# BRD9057A_SiWx917M_4-Layer_ExtSw_REF_DES_.net
KiCad netlist of a schematic drawn in Altium Designer
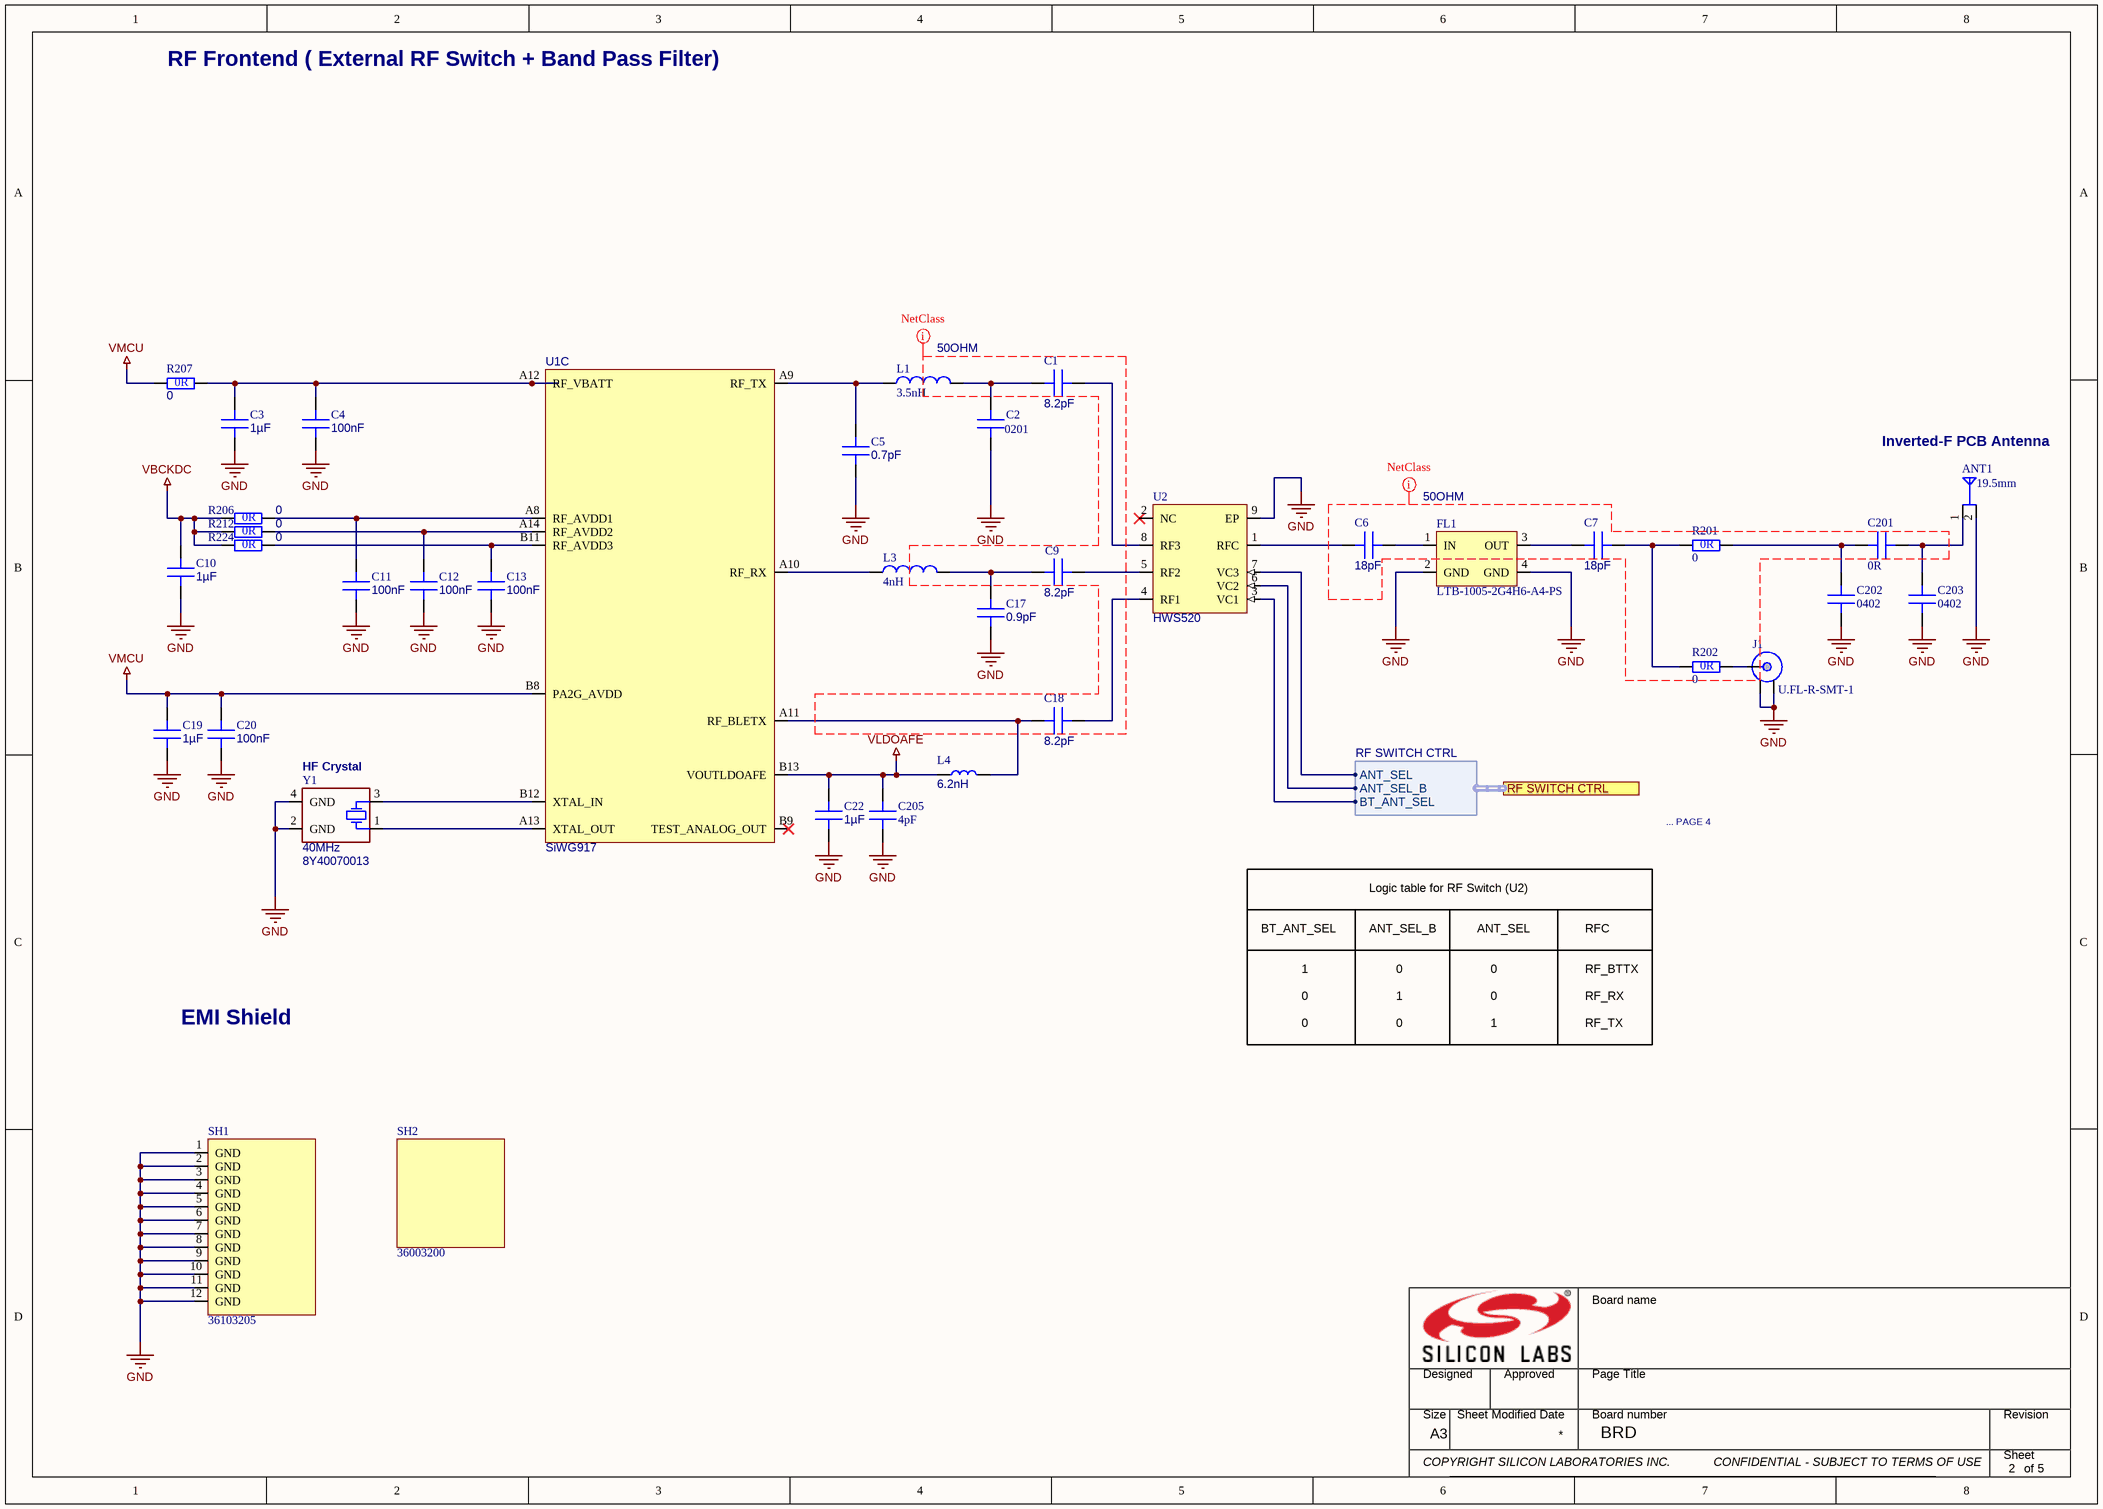
[diagram p0: BRD9057A_SiWx917M_4-Layer_ExtSw_REF_DES_A01_Page_2.SchDoc]

(export (version "E")
  (design (tool "Eeschema 10.0.6"))
  (components
    (comp (ref "ANT1")
      (value "19.5mm")
      (footprint "EM358x_INVERTED_F")
      (description "ANT PATCH 19.5MM INVERTED-F")
      (fields (field (name "Comment") "PATCH ANT INVERTED-F"))
      (libsource (lib "SiLabs Production Server") (part "Patch_Antenna 2-Pin(NO BOM)"))
    )
    (comp (ref "C1")
      (value "8.2pF")
      (footprint "C0201_GM")
      (description "CAP CER 0201 C0G 8.2pF 25V ±0.1pF")
      (fields (field (name "TOLERANCE") "0.1pF") (field (name "MANUFACTURER") "Murata"))
      (libsource (lib "SiLabs Production Server") (part "Capacitor"))
    )
    (comp (ref "C2")
      (value "0201")
      (footprint "C0201_GM")
      (description "Placeholder for 0201 Capacitors")
      (fields (field (name "Comment") "TBD CAP 0201"))
      (libsource (lib "SiLabs Production Server") (part "Placeholder for Capacitor"))
    )
    (comp (ref "C3")
      (value "1µF")
      (footprint "C0201_GM")
      (description "CAP CER 0201 X5R 1uF 16V 20%")
      (fields (field (name "TOLERANCE") "20%"))
      (libsource (lib "SiLabs Production Server") (part "Capacitor"))
    )
    (comp (ref "C4")
      (value "100nF")
      (footprint "C0201_GM")
      (description "CAP CER 0201 X5R 100nF 16V 10%")
      (fields (field (name "TOLERANCE") "10%"))
      (libsource (lib "SiLabs Production Server") (part "Capacitor"))
    )
    (comp (ref "C5")
      (value "0.7pF")
      (footprint "C0201_GM")
      (description "CAP CER 0201 C0G 0.7pF 50V ±0.05pF")
      (fields (field (name "MANUFACTURER") "Murata") (field (name "TOLERANCE") "0.05pF"))
      (libsource (lib "BRD9057A SiWx917 4-layer Ext Switch") (part "GRM0335C1HR70WA01"))
    )
    (comp (ref "C6")
      (value "18pF")
      (footprint "C0201_GM")
      (description "CAP CER 0201 C0G 18pF 50V 2%")
      (fields (field (name "TOLERANCE") "2%") (field (name "MANUFACTURER") "Murata"))
      (libsource (lib "SiLabs Production Server") (part "Capacitor"))
    )
    (comp (ref "C7")
      (value "18pF")
      (footprint "C0201_GM")
      (description "CAP CER 0201 C0G 18pF 50V 2%")
      (fields (field (name "TOLERANCE") "2%") (field (name "MANUFACTURER") "Murata"))
      (libsource (lib "SiLabs Production Server") (part "Capacitor"))
    )
    (comp (ref "C9")
      (value "8.2pF")
      (footprint "C0201_GM")
      (description "CAP CER 0201 C0G 8.2pF 25V ±0.1pF")
      (fields (field (name "TOLERANCE") "0.1pF") (field (name "MANUFACTURER") "Murata"))
      (libsource (lib "SiLabs Production Server") (part "Capacitor"))
    )
    (comp (ref "C10")
      (value "1µF")
      (footprint "C0201_GM")
      (description "CAP CER 0201 X5R 1uF 16V 20%")
      (fields (field (name "TOLERANCE") "20%"))
      (libsource (lib "SiLabs Production Server") (part "Capacitor"))
    )
    (comp (ref "C11")
      (value "100nF")
      (footprint "C0201_GM")
      (description "CAP CER 0201 X5R 100nF 16V 10%")
      (fields (field (name "TOLERANCE") "10%"))
      (libsource (lib "SiLabs Production Server") (part "Capacitor"))
    )
    (comp (ref "C12")
      (value "100nF")
      (footprint "C0201_GM")
      (description "CAP CER 0201 X5R 100nF 16V 10%")
      (fields (field (name "TOLERANCE") "10%"))
      (libsource (lib "SiLabs Production Server") (part "Capacitor"))
    )
    (comp (ref "C13")
      (value "100nF")
      (footprint "C0201_GM")
      (description "CAP CER 0201 X5R 100nF 16V 10%")
      (fields (field (name "TOLERANCE") "10%"))
      (libsource (lib "SiLabs Production Server") (part "Capacitor"))
    )
    (comp (ref "C17")
      (value "0.9pF")
      (footprint "C0201_GM")
      (description "CAP CER 0201 C0G 0.9pF 50V ±0.05pF")
      (fields (field (name "MANUFACTURER") "Murata") (field (name "TOLERANCE") "0.05pF"))
      (libsource (lib "BRD9057A SiWx917 4-layer Ext Switch") (part "GRM0335C1HR90WA01"))
    )
    (comp (ref "C18")
      (value "8.2pF")
      (footprint "C0201_GM")
      (description "CAP CER 0201 C0G 8.2pF 25V ±0.1pF")
      (fields (field (name "TOLERANCE") "0.1pF") (field (name "MANUFACTURER") "Murata"))
      (libsource (lib "SiLabs Production Server") (part "Capacitor"))
    )
    (comp (ref "C19")
      (value "1µF")
      (footprint "C0201_GM")
      (description "CAP CER 0201 X5R 1uF 16V 20%")
      (fields (field (name "TOLERANCE") "20%"))
      (libsource (lib "SiLabs Production Server") (part "Capacitor"))
    )
    (comp (ref "C20")
      (value "100nF")
      (footprint "C0201_GM")
      (description "CAP CER 0201 X5R 100nF 16V 10%")
      (fields (field (name "TOLERANCE") "10%"))
      (libsource (lib "SiLabs Production Server") (part "Capacitor"))
    )
    (comp (ref "C22")
      (value "1µF")
      (footprint "C0201_GM")
      (description "CAP CER 0201 X5R 1uF 16V 20%")
      (fields (field (name "TOLERANCE") "20%"))
      (libsource (lib "SiLabs Production Server") (part "Capacitor"))
    )
    (comp (ref "C201")
      (value "0R")
      (footprint "C0402")
      (description "Placeholder for 0402 Capacitors")
      (fields (field (name "Comment") "TBD CAP 0402"))
      (libsource (lib "SiLabs Production Server") (part "Placeholder for Capacitor"))
    )
    (comp (ref "C202")
      (value "0402")
      (footprint "C0402")
      (description "Placeholder for 0402 Capacitors")
      (fields (field (name "Comment") "TBD CAP 0402"))
      (libsource (lib "SiLabs Production Server") (part "Placeholder for Capacitor"))
    )
    (comp (ref "C203")
      (value "0402")
      (footprint "C0402")
      (description "Placeholder for 0402 Capacitors")
      (fields (field (name "Comment") "TBD CAP 0402"))
      (libsource (lib "SiLabs Production Server") (part "Placeholder for Capacitor"))
    )
    (comp (ref "C205")
      (value "4pF")
      (footprint "C0201_GM")
      (description "CAP CER 0201 C0G 4pF 25V 0.05pF")
      (fields (field (name "TOLERANCE") "0.05pF"))
      (libsource (lib "SiLabs Production Server") (part "Capacitor"))
    )
    (comp (ref "FL1")
      (value "LTB-1005-2G4H6-A4-PS")
      (footprint "BPF_LTB-1005-2G4H6-A2-PS_GM")
      (description "FILTER BAND PASS 0402-4Pin 2.45GHz 100MHz")
      (fields (field (name "MANUFACTURER") "Maglayers"))
      (libsource (lib "SiLabs Production Server") (part "FILTER-1-3-4P"))
    )
    (comp (ref "J1")
      (value "U.FL-R-SMT-1")
      (footprint "KLS1-IPEX_2.6x2.6")
      (description "CONN RF 50OHM UFL_2.6x2.6 SMD")
      (fields (field (name "MANUFACTURER") "Hirose"))
      (libsource (lib "SiLabs Production Server") (part "CONN COAX"))
    )
    (comp (ref "L1")
      (value "3.5nH")
      (footprint "COIL_0201_GM")
      (description "IND Fixed 0201 3.5nH 500mA 170mOhm ±0.1nH")
      (fields (field (name "MANUFACTURER") "Murata") (field (name "TOLERANCE") "0.1nH"))
      (libsource (lib "") (part "Inductor_1"))
    )
    (comp (ref "L3")
      (value "4nH")
      (footprint "COIL_0201_GM")
      (description "IND Fixed 0201 4nH 500mA 170mOhm ±0.1nH")
      (fields (field (name "MANUFACTURER") "Murata") (field (name "TOLERANCE") "0.1nH"))
      (libsource (lib "BRD9057A SiWx917 4-layer Ext Switch") (part "LQP03HQ4N0B02D"))
    )
    (comp (ref "L4")
      (value "6.2nH")
      (footprint "COIL_0201_GM")
      (description "IND Fixed 0201 6.2nH 400mA 250mOhm 3%")
      (fields (field (name "MANUFACTURER") "Murata") (field (name "TOLERANCE") "3%"))
      (libsource (lib "SiLabs Production Server") (part "Inductor"))
    )
    (comp (ref "R201")
      (value "0")
      (footprint "R0402")
      (description "RES 0402 0R")
      (fields (field (name "TOLERANCE") "0%"))
      (libsource (lib "SiLabs Production Server") (part "Resistor-Jumper"))
    )
    (comp (ref "R202")
      (value "0")
      (footprint "R0402")
      (description "RES 0402 0R")
      (fields (field (name "TOLERANCE") "0%"))
      (libsource (lib "SiLabs Production Server") (part "Resistor-Jumper"))
    )
    (comp (ref "R206")
      (value "0")
      (footprint "R0402")
      (description "RES 0402 0R 1/16W 1% 200ppm")
      (fields (field (name "MANUFACTURER") "Yageo") (field (name "TOLERANCE") "1%"))
      (libsource (lib "SiLabs Production Server") (part "Resistor-Jumper"))
    )
    (comp (ref "R207")
      (value "0")
      (footprint "R0402")
      (description "RES 0402 0R 1/16W 1% 200ppm")
      (fields (field (name "MANUFACTURER") "Yageo") (field (name "TOLERANCE") "1%"))
      (libsource (lib "SiLabs Production Server") (part "Resistor-Jumper"))
    )
    (comp (ref "R212")
      (value "0")
      (footprint "R0402")
      (description "RES 0402 0R 1/16W 1% 200ppm")
      (fields (field (name "MANUFACTURER") "Yageo") (field (name "TOLERANCE") "1%"))
      (libsource (lib "SiLabs Production Server") (part "Resistor-Jumper"))
    )
    (comp (ref "R224")
      (value "0")
      (footprint "R0402")
      (description "RES 0402 0R 1/16W 1% 200ppm")
      (fields (field (name "MANUFACTURER") "Yageo") (field (name "TOLERANCE") "1%"))
      (libsource (lib "SiLabs Production Server") (part "Resistor-Jumper"))
    )
    (comp (ref "SH1")
      (value "36103205")
      (footprint "WURTH_36103205_No_Paste")
      (description "SHIELD FRAME 21x21x3 STEEL 0.5")
      (fields (field (name "MANUFACTURER") "Würth Elektronik"))
      (libsource (lib "SiLabs Production Server") (part "RF_SHIELD_FRAME_12PIN"))
    )
    (comp (ref "SH2")
      (value "36003200")
      (description "SHIELD COVER 21.8x21.8x3 STEEL 0.3")
      (fields (field (name "MANUFACTURER") "Würth Elektronik"))
      (libsource (lib "SiLabs Production Server") (part "RF_SHIELD_COVER"))
    )
    (comp (ref "U1")
      (value "SiWG917")
      (footprint "QFN84_SI_SiWx917_A1")
      (description "IC SoC 32BIT 8MB FLASH QFN84 2.4GHz Single Band Wi-Fi")
      (fields (field (name "MANUFACTURER") "Silicon Labs") (field (name "VOLTAGE") "3.63V"))
      (libsource (lib "SiLabs Production Server") (part "SiWx917"))
    )
    (comp (ref "U2")
      (value "HWS520")
      (footprint "USON8L_1.5X1.5MM_GM")
      (description "IC RF SWITCH SP3T 6GHz USON8L")
      (fields (field (name "MANUFACTURER") "Hexawave") (field (name "VOLTAGE") "6V"))
      (libsource (lib "SiLabs Production Server") (part "HWS520"))
    )
    (comp (ref "Y1")
      (value "40MHz")
      (footprint "XTAL200X160X50")
      (description "CRYSTAL 2.0X1.6mm 40MHz 8pF 8ppm")
      (fields
        (field (name "MANUFACTURER PN") "8Y40070013")
        (field (name "MANUFACTURER") "TXC")
        (field (name "TOLERANCE") "8ppm")
      )
      (libsource (lib "SiLabs Production Server") (part "XTAL-1-3-4P"))
    )
  )
  (nets
    (net (code "4") (name "/ANT_SEL") (class "Default")
      (node (ref "U2") (pin "7") (pinfunction "VC3_7") (pintype "input"))
    )
    (net (code "5") (name "/ANT_SEL_B") (class "Default")
      (node (ref "U2") (pin "6") (pinfunction "VC2_6") (pintype "input"))
    )
    (net (code "6") (name "/BT_ANT_SEL") (class "Default")
      (node (ref "U2") (pin "3") (pinfunction "VC1_3") (pintype "input"))
    )
    (net (code "8") (name "GND") (class "Default")
      (node (ref "ANT1") (pin "2") (pinfunction "2_2") (pintype "passive"))
      (node (ref "C10") (pin "1") (pinfunction "1_1") (pintype "passive"))
      (node (ref "C11") (pin "1") (pinfunction "1_1") (pintype "passive"))
      (node (ref "C12") (pin "1") (pinfunction "1_1") (pintype "passive"))
      (node (ref "C13") (pin "1") (pinfunction "1_1") (pintype "passive"))
      (node (ref "C17") (pin "1") (pinfunction "1_1") (pintype "passive"))
      (node (ref "C19") (pin "1") (pinfunction "1_1") (pintype "passive"))
      (node (ref "C2") (pin "2") (pinfunction "2_2") (pintype "passive"))
      (node (ref "C20") (pin "1") (pinfunction "1_1") (pintype "passive"))
      (node (ref "C202") (pin "1") (pinfunction "1_1") (pintype "passive"))
      (node (ref "C203") (pin "1") (pinfunction "1_1") (pintype "passive"))
      (node (ref "C205") (pin "1") (pinfunction "1_1") (pintype "passive"))
      (node (ref "C22") (pin "1") (pinfunction "1_1") (pintype "passive"))
      (node (ref "C3") (pin "1") (pinfunction "1_1") (pintype "passive"))
      (node (ref "C4") (pin "1") (pinfunction "1_1") (pintype "passive"))
      (node (ref "C5") (pin "1") (pinfunction "1_1") (pintype "passive"))
      (node (ref "FL1") (pin "2") (pinfunction "GND_2") (pintype "power_in"))
      (node (ref "FL1") (pin "4") (pinfunction "GND_4") (pintype "power_in"))
      (node (ref "J1") (pin "2") (pinfunction "SHIELD_2") (pintype "passive"))
      (node (ref "J1") (pin "3") (pinfunction "SHIELD_3") (pintype "passive"))
      (node (ref "SH1") (pin "1") (pinfunction "GND_1") (pintype "passive"))
      (node (ref "SH1") (pin "10") (pinfunction "GND_10") (pintype "power_in"))
      (node (ref "SH1") (pin "11") (pinfunction "GND_11") (pintype "power_in"))
      (node (ref "SH1") (pin "12") (pinfunction "GND_12") (pintype "power_in"))
      (node (ref "SH1") (pin "2") (pinfunction "GND_2") (pintype "power_in"))
      (node (ref "SH1") (pin "3") (pinfunction "GND_3") (pintype "power_in"))
      (node (ref "SH1") (pin "4") (pinfunction "GND_4") (pintype "power_in"))
      (node (ref "SH1") (pin "5") (pinfunction "GND_5") (pintype "power_in"))
      (node (ref "SH1") (pin "6") (pinfunction "GND_6") (pintype "power_in"))
      (node (ref "SH1") (pin "7") (pinfunction "GND_7") (pintype "power_in"))
      (node (ref "SH1") (pin "8") (pinfunction "GND_8") (pintype "power_in"))
      (node (ref "SH1") (pin "9") (pinfunction "GND_9") (pintype "power_in"))
      (node (ref "U2") (pin "9") (pinfunction "EP_9") (pintype "power_in"))
      (node (ref "Y1") (pin "2") (pinfunction "GND_2") (pintype "power_in"))
      (node (ref "Y1") (pin "4") (pinfunction "GND_4") (pintype "power_in"))
    )
    (net (code "9") (name "Net-(ANT1-Pad1)") (class "Default")
      (node (ref "ANT1") (pin "1") (pinfunction "1_1") (pintype "passive"))
      (node (ref "C201") (pin "2") (pinfunction "2_2") (pintype "passive"))
      (node (ref "C203") (pin "2") (pinfunction "2_2") (pintype "passive"))
    )
    (net (code "10") (name "Net-(C1-Pad1)") (class "Default")
      (node (ref "C1") (pin "1") (pinfunction "1_1") (pintype "passive"))
      (node (ref "C2") (pin "1") (pinfunction "1_1") (pintype "passive"))
      (node (ref "L1") (pin "2") (pinfunction "2_2") (pintype "passive"))
    )
    (net (code "11") (name "Net-(C7-Pad2)") (class "Default")
      (node (ref "C7") (pin "2") (pinfunction "2_2") (pintype "passive"))
      (node (ref "R201") (pin "1") (pinfunction "1_1") (pintype "passive"))
      (node (ref "R202") (pin "1") (pinfunction "1_1") (pintype "passive"))
    )
    (net (code "12") (name "Net-(C17-Pad2)") (class "Default")
      (node (ref "C17") (pin "2") (pinfunction "2_2") (pintype "passive"))
      (node (ref "C9") (pin "1") (pinfunction "1_1") (pintype "passive"))
      (node (ref "L3") (pin "2") (pinfunction "2_2") (pintype "passive"))
    )
    (net (code "13") (name "Net-(C201-Pad1)") (class "Default")
      (node (ref "C201") (pin "1") (pinfunction "1_1") (pintype "passive"))
      (node (ref "C202") (pin "2") (pinfunction "2_2") (pintype "passive"))
      (node (ref "R201") (pin "2") (pinfunction "2_2") (pintype "passive"))
    )
    (net (code "14") (name "Net-(FL1-IN)") (class "Default")
      (node (ref "C6") (pin "2") (pinfunction "2_2") (pintype "passive"))
      (node (ref "FL1") (pin "1") (pinfunction "IN_1") (pintype "passive"))
    )
    (net (code "15") (name "Net-(FL1-OUT)") (class "Default")
      (node (ref "C7") (pin "1") (pinfunction "1_1") (pintype "passive"))
      (node (ref "FL1") (pin "3") (pinfunction "OUT_3") (pintype "passive"))
    )
    (net (code "16") (name "Net-(J1-CENTER)") (class "Default")
      (node (ref "J1") (pin "1") (pinfunction "CENTER_1") (pintype "passive"))
      (node (ref "R202") (pin "2") (pinfunction "2_2") (pintype "passive"))
    )
    (net (code "17") (name "Net-(U1C-RF_AVDD1)") (class "Default")
      (node (ref "C11") (pin "2") (pinfunction "2_2") (pintype "passive"))
      (node (ref "R206") (pin "2") (pinfunction "2_2") (pintype "passive"))
      (node (ref "U1") (pin "A8") (pinfunction "RF_AVDD1_A8") (pintype "power_in"))
    )
    (net (code "18") (name "Net-(U1C-RF_AVDD2)") (class "Default")
      (node (ref "C12") (pin "2") (pinfunction "2_2") (pintype "passive"))
      (node (ref "R212") (pin "2") (pinfunction "2_2") (pintype "passive"))
      (node (ref "U1") (pin "A14") (pinfunction "RF_AVDD2_A14") (pintype "power_in"))
    )
    (net (code "19") (name "Net-(U1C-RF_AVDD3)") (class "Default")
      (node (ref "C13") (pin "2") (pinfunction "2_2") (pintype "passive"))
      (node (ref "R224") (pin "2") (pinfunction "2_2") (pintype "passive"))
      (node (ref "U1") (pin "B11") (pinfunction "RF_AVDD3_B11") (pintype "power_in"))
    )
    (net (code "20") (name "Net-(U1C-RF_BLETX)") (class "Default")
      (node (ref "C18") (pin "1") (pinfunction "1_1") (pintype "passive"))
      (node (ref "L4") (pin "2") (pinfunction "2_2") (pintype "passive"))
      (node (ref "U1") (pin "A11") (pinfunction "RF_BLETX_A11") (pintype "passive"))
    )
    (net (code "21") (name "Net-(U1C-RF_RX)") (class "Default")
      (node (ref "L3") (pin "1") (pinfunction "1_1") (pintype "passive"))
      (node (ref "U1") (pin "A10") (pinfunction "RF_RX_A10") (pintype "passive"))
    )
    (net (code "22") (name "Net-(U1C-RF_TX)") (class "Default")
      (node (ref "C5") (pin "2") (pinfunction "2_2") (pintype "passive"))
      (node (ref "L1") (pin "1") (pinfunction "1_1") (pintype "passive"))
      (node (ref "U1") (pin "A9") (pinfunction "RF_TX_A9") (pintype "passive"))
    )
    (net (code "23") (name "Net-(U1C-RF_VBATT)") (class "Default")
      (node (ref "C3") (pin "2") (pinfunction "2_2") (pintype "passive"))
      (node (ref "C4") (pin "2") (pinfunction "2_2") (pintype "passive"))
      (node (ref "R207") (pin "2") (pinfunction "2_2") (pintype "passive"))
      (node (ref "U1") (pin "A12") (pinfunction "RF_VBATT_A12") (pintype "power_in"))
    )
    (net (code "24") (name "Net-(U1C-XTAL_IN)") (class "Default")
      (node (ref "U1") (pin "B12") (pinfunction "XTAL_IN_B12") (pintype "passive"))
      (node (ref "Y1") (pin "3") (pinfunction "X2_3") (pintype "passive"))
    )
    (net (code "25") (name "Net-(U1C-XTAL_OUT)") (class "Default")
      (node (ref "U1") (pin "A13") (pinfunction "XTAL_OUT_A13") (pintype "passive"))
      (node (ref "Y1") (pin "1") (pinfunction "X1_1") (pintype "passive"))
    )
    (net (code "26") (name "Net-(U2-RF1)") (class "Default")
      (node (ref "C18") (pin "2") (pinfunction "2_2") (pintype "passive"))
      (node (ref "U2") (pin "4") (pinfunction "RF1_4") (pintype "passive"))
    )
    (net (code "27") (name "Net-(U2-RF2)") (class "Default")
      (node (ref "C9") (pin "2") (pinfunction "2_2") (pintype "passive"))
      (node (ref "U2") (pin "5") (pinfunction "RF2_5") (pintype "passive"))
    )
    (net (code "28") (name "Net-(U2-RF3)") (class "Default")
      (node (ref "C1") (pin "2") (pinfunction "2_2") (pintype "passive"))
      (node (ref "U2") (pin "8") (pinfunction "RF3_8") (pintype "passive"))
    )
    (net (code "29") (name "Net-(U2-RFC)") (class "Default")
      (node (ref "C6") (pin "1") (pinfunction "1_1") (pintype "passive"))
      (node (ref "U2") (pin "1") (pinfunction "RFC_1") (pintype "passive"))
    )
    (net (code "30") (name "VBCKDC") (class "Default")
      (node (ref "C10") (pin "2") (pinfunction "2_2") (pintype "passive"))
      (node (ref "R206") (pin "1") (pinfunction "1_1") (pintype "passive"))
      (node (ref "R212") (pin "1") (pinfunction "1_1") (pintype "passive"))
      (node (ref "R224") (pin "1") (pinfunction "1_1") (pintype "passive"))
    )
    (net (code "31") (name "VLDOAFE") (class "Default")
      (node (ref "C205") (pin "2") (pinfunction "2_2") (pintype "passive"))
      (node (ref "C22") (pin "2") (pinfunction "2_2") (pintype "passive"))
      (node (ref "L4") (pin "1") (pinfunction "1_1") (pintype "passive"))
      (node (ref "U1") (pin "B13") (pinfunction "VOUTLDOAFE_B13") (pintype "power_in"))
    )
    (net (code "32") (name "VMCU") (class "Default")
      (node (ref "C19") (pin "2") (pinfunction "2_2") (pintype "passive"))
      (node (ref "C20") (pin "2") (pinfunction "2_2") (pintype "passive"))
      (node (ref "R207") (pin "1") (pinfunction "1_1") (pintype "passive"))
      (node (ref "U1") (pin "B8") (pinfunction "PA2G_AVDD_B8") (pintype "power_in"))
    )
    (net (code "33") (name "unconnected-(U1C-TEST_ANALOG_OUT-PadB9)") (class "Default")
      (node (ref "U1") (pin "B9") (pinfunction "TEST_ANALOG_OUT_B9") (pintype "passive+no_connect"))
    )
    (net (code "34") (name "unconnected-(U2-NC-Pad2)") (class "Default")
      (node (ref "U2") (pin "2") (pinfunction "NC_2") (pintype "passive+no_connect"))
    )
  )
)
